# esp-switchnode-02.net
KiCad netlist of a schematic drawn in EAGLE
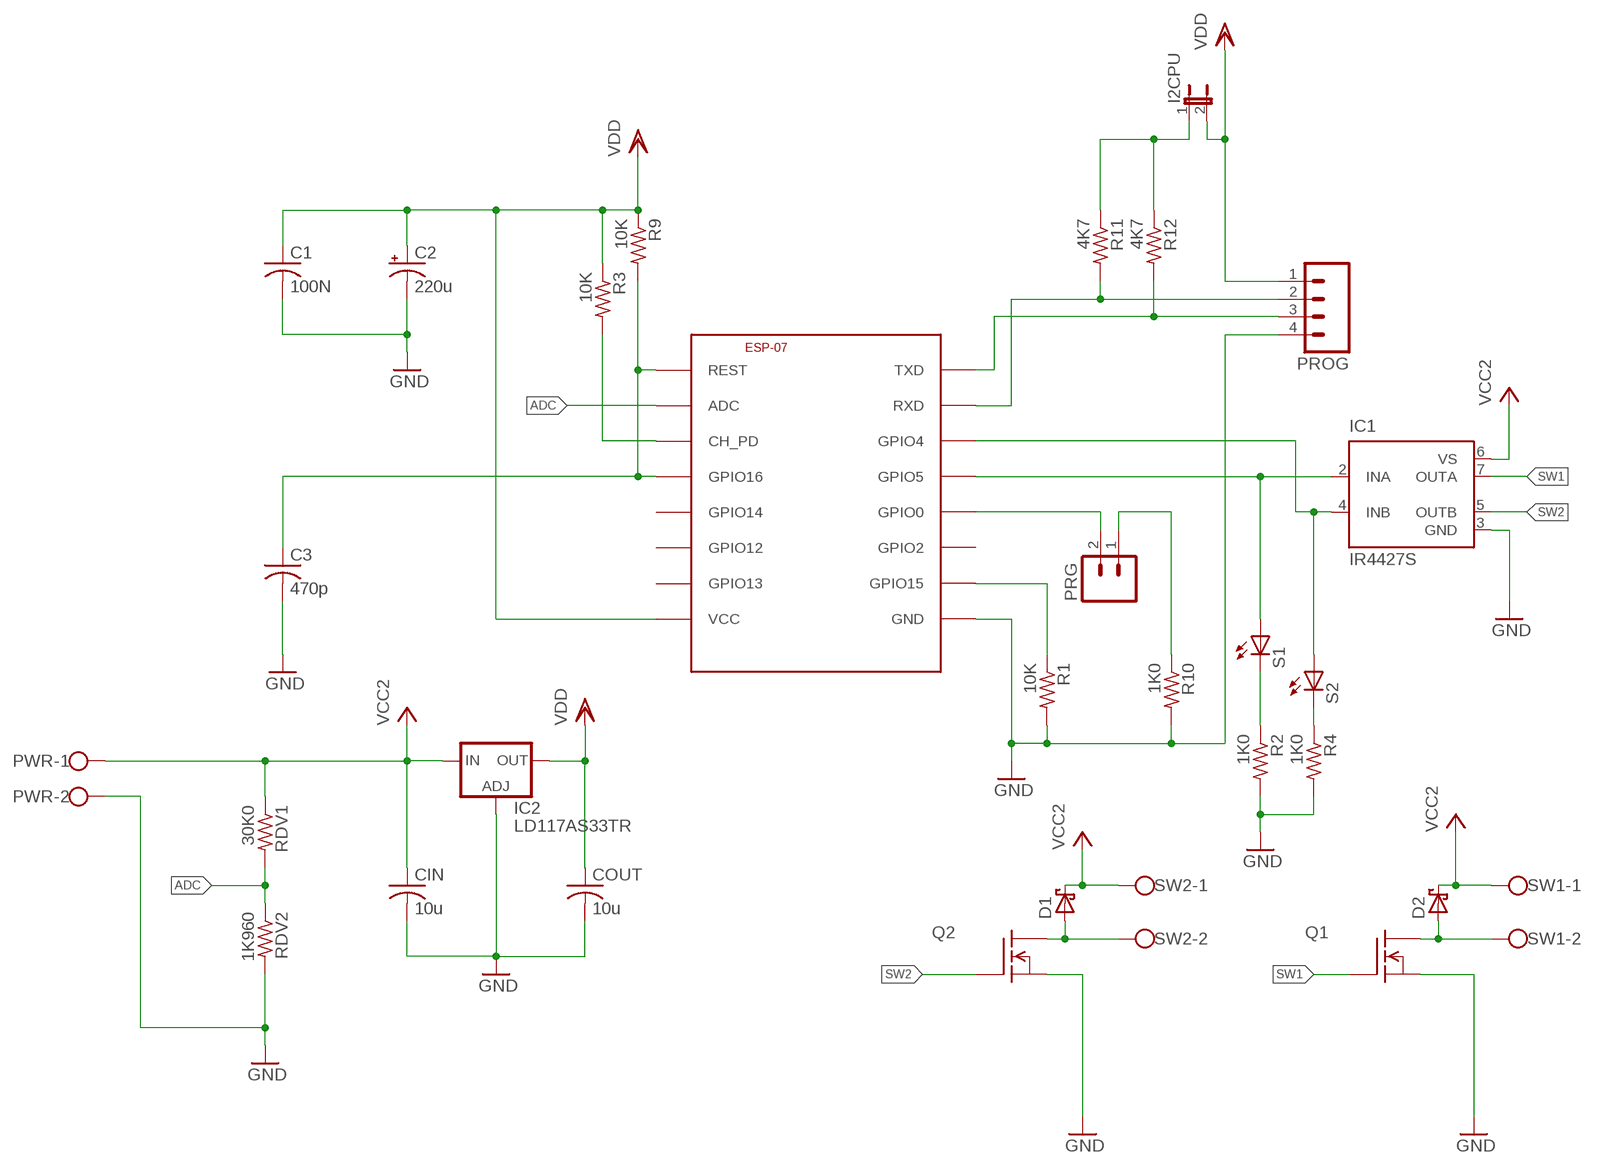
[diagram p0: schematic, sheet 1]

(export (version "E")
  (design (tool "Eeschema 10.0.6"))
  (components
    (comp (ref "C1")
      (value "100N")
      (footprint "eagle-import:C0603")
      (libsource (lib "eagle-import") (part "C-USC0603"))
    )
    (comp (ref "C2")
      (value "220u")
      (footprint "eagle-import:SMC_D")
      (libsource (lib "eagle-import") (part "CPOL-USSMCD"))
    )
    (comp (ref "C3")
      (value "470p")
      (footprint "eagle-import:C0603")
      (libsource (lib "eagle-import") (part "C-USC0603"))
    )
    (comp (ref "CIN")
      (value "10u")
      (footprint "eagle-import:C1210")
      (libsource (lib "eagle-import") (part "C-USC1210"))
    )
    (comp (ref "COUT")
      (value "10u")
      (footprint "eagle-import:C1206")
      (libsource (lib "eagle-import") (part "C-USC1206"))
    )
    (comp (ref "D1")
      (value "SCHOTTKY-SOD123")
      (footprint "eagle-import:SOD123")
      (libsource (lib "eagle-import") (part "SCHOTTKY-SOD123"))
    )
    (comp (ref "D2")
      (value "SCHOTTKY-SOD123")
      (footprint "eagle-import:SOD123")
      (libsource (lib "eagle-import") (part "SCHOTTKY-SOD123"))
    )
    (comp (ref "ESP-07")
      (value "ESP8266-07")
      (footprint "eagle-import:ESP-07")
      (libsource (lib "eagle-import") (part "ESP8266-07"))
    )
    (comp (ref "I2CPU")
      (value "JUMPER-2SMD-NO")
      (footprint "eagle-import:SJ_2S-NO")
      (libsource (lib "eagle-import") (part "JUMPER-2SMD-NO"))
    )
    (comp (ref "IC1")
      (value "IR4427S")
      (footprint "eagle-import:SO08")
      (fields (field (name "MF") "INTERNATIONAL RECTIFIER(IR)") (field (name "MPN") "IR4427STRPBF"))
      (libsource (lib "eagle-import") (part "IR4427S"))
    )
    (comp (ref "IC2")
      (value "LD117AS33TR")
      (footprint "eagle-import:SOT223")
      (libsource (lib "eagle-import") (part "LD117A?S33TR"))
    )
    (comp (ref "PRG")
      (value "M02LOCK")
      (footprint "eagle-import:1X02_LOCK")
      (libsource (lib "eagle-import") (part "M02LOCK"))
    )
    (comp (ref "PROG")
      (value "M04LOCK")
      (footprint "eagle-import:1X04_LOCK")
      (libsource (lib "eagle-import") (part "M04LOCK"))
    )
    (comp (ref "PWR")
      (value "W237-102")
      (footprint "eagle-import:W237-102")
      (fields (field (name "MPN") "237-102"))
      (libsource (lib "eagle-import") (part "W237-102"))
    )
    (comp (ref "Q1")
      (value "NFET-TO252")
      (footprint "eagle-import:TO252")
      (libsource (lib "eagle-import") (part "NFET-TO252"))
    )
    (comp (ref "Q2")
      (value "NFET-TO252")
      (footprint "eagle-import:TO252")
      (libsource (lib "eagle-import") (part "NFET-TO252"))
    )
    (comp (ref "R1")
      (value "10K")
      (footprint "eagle-import:R0603")
      (libsource (lib "eagle-import") (part "R-US_R0603"))
    )
    (comp (ref "R2")
      (value "1K0")
      (footprint "eagle-import:R0603")
      (libsource (lib "eagle-import") (part "R-US_R0603"))
    )
    (comp (ref "R3")
      (value "10K")
      (footprint "eagle-import:R0603")
      (libsource (lib "eagle-import") (part "R-US_R0603"))
    )
    (comp (ref "R4")
      (value "1K0")
      (footprint "eagle-import:R0603")
      (libsource (lib "eagle-import") (part "R-US_R0603"))
    )
    (comp (ref "R9")
      (value "10K")
      (footprint "eagle-import:R0603")
      (libsource (lib "eagle-import") (part "R-US_R0603"))
    )
    (comp (ref "R10")
      (value "1K0")
      (footprint "eagle-import:R0603")
      (libsource (lib "eagle-import") (part "R-US_R0603"))
    )
    (comp (ref "R11")
      (value "4K7")
      (footprint "eagle-import:R0603")
      (libsource (lib "eagle-import") (part "R-US_R0603"))
    )
    (comp (ref "R12")
      (value "4K7")
      (footprint "eagle-import:R0603")
      (libsource (lib "eagle-import") (part "R-US_R0603"))
    )
    (comp (ref "RDV1")
      (value "30K0")
      (footprint "eagle-import:R0603")
      (libsource (lib "eagle-import") (part "R-US_R0603"))
    )
    (comp (ref "RDV2")
      (value "1K960")
      (footprint "eagle-import:R0603")
      (libsource (lib "eagle-import") (part "R-US_R0603"))
    )
    (comp (ref "S1")
      (value "LEDCHIPLED_0805")
      (footprint "eagle-import:CHIPLED_0805")
      (libsource (lib "eagle-import") (part "LEDCHIPLED_0805"))
    )
    (comp (ref "S2")
      (value "LEDCHIPLED_0805")
      (footprint "eagle-import:CHIPLED_0805")
      (libsource (lib "eagle-import") (part "LEDCHIPLED_0805"))
    )
    (comp (ref "SW1")
      (value "W237-102")
      (footprint "eagle-import:W237-102")
      (fields (field (name "MPN") "237-102"))
      (libsource (lib "eagle-import") (part "W237-102"))
    )
    (comp (ref "SW2")
      (value "W237-102")
      (footprint "eagle-import:W237-102")
      (fields (field (name "MPN") "237-102"))
      (libsource (lib "eagle-import") (part "W237-102"))
    )
  )
  (nets
    (net (code "1") (name "ADC") (class "Default")
      (node (ref "ESP-07") (pin "ADC") (pinfunction "ADC_ADC") (pintype "bidirectional"))
      (node (ref "RDV1") (pin "2") (pinfunction "2_2") (pintype "passive"))
      (node (ref "RDV2") (pin "1") (pinfunction "1_1") (pintype "passive"))
    )
    (net (code "2") (name "GND") (class "Default")
      (node (ref "C1") (pin "2") (pinfunction "2_2") (pintype "passive"))
      (node (ref "C2") (pin "-") (pinfunction "-_-") (pintype "passive"))
      (node (ref "C3") (pin "2") (pinfunction "2_2") (pintype "passive"))
      (node (ref "CIN") (pin "2") (pinfunction "2_2") (pintype "passive"))
      (node (ref "COUT") (pin "2") (pinfunction "2_2") (pintype "passive"))
      (node (ref "ESP-07") (pin "GND") (pinfunction "GND_GND") (pintype "power_in"))
      (node (ref "IC1") (pin "3") (pinfunction "GND_3") (pintype "power_in"))
      (node (ref "IC2") (pin "1") (pinfunction "ADJ_1") (pintype "input"))
      (node (ref "PROG") (pin "4") (pinfunction "4_4") (pintype "passive"))
      (node (ref "PWR") (pin "2") (pinfunction "KL_2") (pintype "passive"))
      (node (ref "Q1") (pin "2") (pinfunction "S_2") (pintype "passive"))
      (node (ref "Q2") (pin "2") (pinfunction "S_2") (pintype "passive"))
      (node (ref "R1") (pin "2") (pinfunction "2_2") (pintype "passive"))
      (node (ref "R10") (pin "2") (pinfunction "2_2") (pintype "passive"))
      (node (ref "R2") (pin "2") (pinfunction "2_2") (pintype "passive"))
      (node (ref "R4") (pin "2") (pinfunction "2_2") (pintype "passive"))
      (node (ref "RDV2") (pin "2") (pinfunction "2_2") (pintype "passive"))
    )
    (net (code "3") (name "Net-(C3-Pad1)") (class "Default")
      (node (ref "C3") (pin "1") (pinfunction "1_1") (pintype "passive"))
      (node (ref "ESP-07") (pin "GPIO16") (pinfunction "GPIO16_GPIO16") (pintype "bidirectional"))
      (node (ref "ESP-07") (pin "REST") (pinfunction "REST_REST") (pintype "bidirectional"))
      (node (ref "R9") (pin "2") (pinfunction "2_2") (pintype "passive"))
    )
    (net (code "4") (name "Net-(ESP-07-PadCH_PD)") (class "Default")
      (node (ref "ESP-07") (pin "CH_PD") (pinfunction "CH_PD_CH_PD") (pintype "input"))
      (node (ref "R3") (pin "2") (pinfunction "2_2") (pintype "passive"))
    )
    (net (code "5") (name "Net-(ESP-07-PadGPIO0)") (class "Default")
      (node (ref "ESP-07") (pin "GPIO0") (pinfunction "GPIO0_GPIO0") (pintype "bidirectional"))
      (node (ref "PRG") (pin "2") (pinfunction "2_2") (pintype "passive"))
    )
    (net (code "6") (name "Net-(ESP-07-PadGPIO15)") (class "Default")
      (node (ref "ESP-07") (pin "GPIO15") (pinfunction "GPIO15_GPIO15") (pintype "input"))
      (node (ref "R1") (pin "1") (pinfunction "1_1") (pintype "passive"))
    )
    (net (code "7") (name "Net-(ESP-07-PadRXD)") (class "Default")
      (node (ref "ESP-07") (pin "RXD") (pinfunction "RXD_RXD") (pintype "input"))
      (node (ref "PROG") (pin "2") (pinfunction "2_2") (pintype "passive"))
      (node (ref "R11") (pin "2") (pinfunction "2_2") (pintype "passive"))
    )
    (net (code "8") (name "Net-(ESP-07-PadTXD)") (class "Default")
      (node (ref "ESP-07") (pin "TXD") (pinfunction "TXD_TXD") (pintype "output"))
      (node (ref "PROG") (pin "3") (pinfunction "3_3") (pintype "passive"))
      (node (ref "R12") (pin "2") (pinfunction "2_2") (pintype "passive"))
    )
    (net (code "9") (name "Net-(I2CPU-Pad1)") (class "Default")
      (node (ref "I2CPU") (pin "1") (pinfunction "1_1") (pintype "passive"))
      (node (ref "R11") (pin "1") (pinfunction "1_1") (pintype "passive"))
      (node (ref "R12") (pin "1") (pinfunction "1_1") (pintype "passive"))
    )
    (net (code "10") (name "Net-(IC1-INA)") (class "Default")
      (node (ref "ESP-07") (pin "GPIO5") (pinfunction "GPIO5_GPIO5") (pintype "bidirectional"))
      (node (ref "IC1") (pin "2") (pinfunction "INA_2") (pintype "input"))
      (node (ref "S1") (pin "A") (pinfunction "A_A") (pintype "passive"))
    )
    (net (code "11") (name "Net-(IC1-INB)") (class "Default")
      (node (ref "ESP-07") (pin "GPIO4") (pinfunction "GPIO4_GPIO4") (pintype "bidirectional"))
      (node (ref "IC1") (pin "4") (pinfunction "INB_4") (pintype "input"))
      (node (ref "S2") (pin "A") (pinfunction "A_A") (pintype "passive"))
    )
    (net (code "12") (name "Net-(PRG-Pad1)") (class "Default")
      (node (ref "PRG") (pin "1") (pinfunction "1_1") (pintype "passive"))
      (node (ref "R10") (pin "1") (pinfunction "1_1") (pintype "passive"))
    )
    (net (code "13") (name "Net-(Q1-D)") (class "Default")
      (node (ref "D2") (pin "A") (pinfunction "A_A") (pintype "passive"))
      (node (ref "Q1") (pin "3") (pinfunction "D_3") (pintype "passive"))
      (node (ref "SW1") (pin "2") (pinfunction "KL_2") (pintype "passive"))
    )
    (net (code "14") (name "Net-(Q2-D)") (class "Default")
      (node (ref "D1") (pin "A") (pinfunction "A_A") (pintype "passive"))
      (node (ref "Q2") (pin "3") (pinfunction "D_3") (pintype "passive"))
      (node (ref "SW2") (pin "2") (pinfunction "KL_2") (pintype "passive"))
    )
    (net (code "15") (name "Net-(R2-Pad1)") (class "Default")
      (node (ref "R2") (pin "1") (pinfunction "1_1") (pintype "passive"))
      (node (ref "S1") (pin "C") (pinfunction "C_C") (pintype "passive"))
    )
    (net (code "16") (name "Net-(R4-Pad1)") (class "Default")
      (node (ref "R4") (pin "1") (pinfunction "1_1") (pintype "passive"))
      (node (ref "S2") (pin "C") (pinfunction "C_C") (pintype "passive"))
    )
    (net (code "17") (name "SW1") (class "Default")
      (node (ref "IC1") (pin "7") (pinfunction "OUTA_7") (pintype "output"))
      (node (ref "Q1") (pin "1") (pinfunction "G_1") (pintype "passive"))
    )
    (net (code "18") (name "SW2") (class "Default")
      (node (ref "IC1") (pin "5") (pinfunction "OUTB_5") (pintype "output"))
      (node (ref "Q2") (pin "1") (pinfunction "G_1") (pintype "passive"))
    )
    (net (code "19") (name "VCC2") (class "Default")
      (node (ref "CIN") (pin "1") (pinfunction "1_1") (pintype "passive"))
      (node (ref "D1") (pin "K") (pinfunction "K_K") (pintype "passive"))
      (node (ref "D2") (pin "K") (pinfunction "K_K") (pintype "passive"))
      (node (ref "IC1") (pin "6") (pinfunction "VS_6") (pintype "power_in"))
      (node (ref "IC2") (pin "3") (pinfunction "IN_3") (pintype "input"))
      (node (ref "PWR") (pin "1") (pinfunction "KL_1") (pintype "passive"))
      (node (ref "RDV1") (pin "1") (pinfunction "1_1") (pintype "passive"))
      (node (ref "SW1") (pin "1") (pinfunction "KL_1") (pintype "passive"))
      (node (ref "SW2") (pin "1") (pinfunction "KL_1") (pintype "passive"))
    )
    (net (code "20") (name "VDD") (class "Default")
      (node (ref "C1") (pin "1") (pinfunction "1_1") (pintype "passive"))
      (node (ref "C2") (pin "+") (pinfunction "+_+") (pintype "passive"))
      (node (ref "COUT") (pin "1") (pinfunction "1_1") (pintype "passive"))
      (node (ref "ESP-07") (pin "VCC") (pinfunction "VCC_VCC") (pintype "power_in"))
      (node (ref "I2CPU") (pin "2") (pinfunction "2_2") (pintype "passive"))
      (node (ref "IC2") (pin "4") (pinfunction "OUT_4") (pintype "passive"))
      (node (ref "PROG") (pin "1") (pinfunction "1_1") (pintype "passive"))
      (node (ref "R3") (pin "1") (pinfunction "1_1") (pintype "passive"))
      (node (ref "R9") (pin "1") (pinfunction "1_1") (pintype "passive"))
    )
    (net (code "21") (name "unconnected-(ESP-07-PadGPIO2)") (class "Default")
      (node (ref "ESP-07") (pin "GPIO2") (pinfunction "GPIO2_GPIO2") (pintype "bidirectional"))
    )
    (net (code "22") (name "unconnected-(ESP-07-PadGPIO12)") (class "Default")
      (node (ref "ESP-07") (pin "GPIO12") (pinfunction "GPIO12_GPIO12") (pintype "bidirectional"))
    )
    (net (code "23") (name "unconnected-(ESP-07-PadGPIO13)") (class "Default")
      (node (ref "ESP-07") (pin "GPIO13") (pinfunction "GPIO13_GPIO13") (pintype "bidirectional"))
    )
    (net (code "24") (name "unconnected-(ESP-07-PadGPIO14)") (class "Default")
      (node (ref "ESP-07") (pin "GPIO14") (pinfunction "GPIO14_GPIO14") (pintype "bidirectional"))
    )
  )
)
